# HBridge_Design.net
KiCad netlist of a schematic drawn in Altium Designer
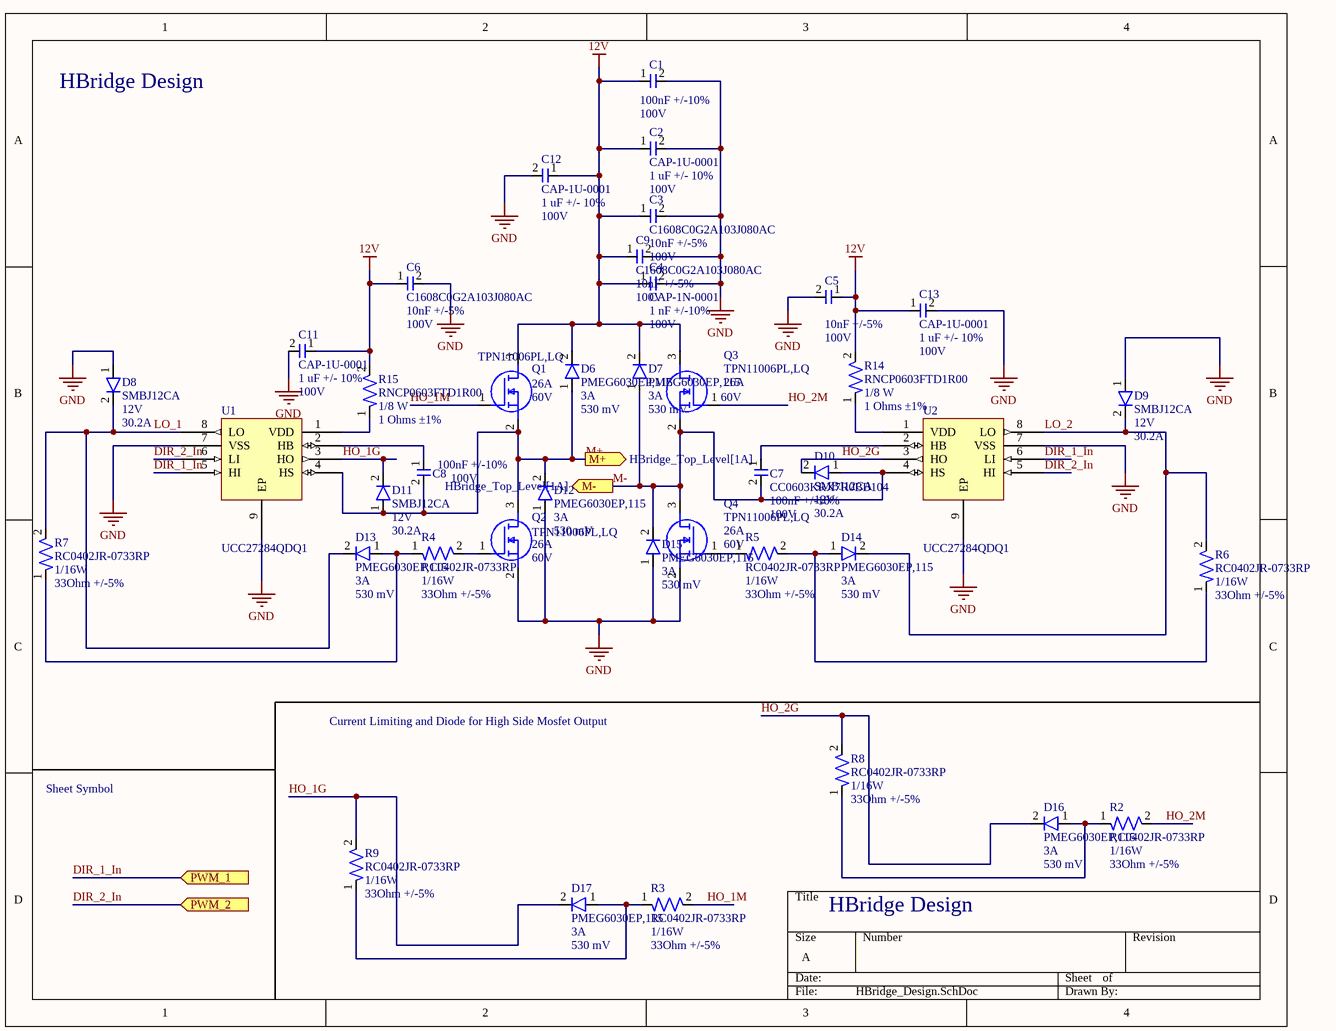
[diagram p0: HBridge_Design.SchDoc]

(export (version "E")
  (design (tool "Eeschema 10.0.6"))
  (components
    (comp (ref "C1")
      (value "CC0603KRX7R0BB104")
      (footprint "CAP-0603")
      (description "CAP CER 0.1UF 100V X7R 0603")
      (fields
        (field (name "MANUFACTURER") "YAGEO")
        (field (name "CAPACITANCE") "100nF +/-10%")
        (field (name "VOLTAGE RATING") "100V")
      )
      (libsource (lib "MasterLib") (part "CAP-100N-0001"))
    )
    (comp (ref "C2")
      (value "CAP-1U-0001")
      (footprint "CAP-1206 - duplicate")
      (description "1 µF ±10% 100V Ceramic Capacitor X7R 1206 (3216 Metric)")
      (fields (field (name "CAPACITANCE") "1 uF +/- 10%") (field (name "VOLTAGE") "100V"))
      (libsource (lib "MasterLib") (part "CAP-1U-0001"))
    )
    (comp (ref "C3")
      (value "C1608C0G2A103J080AC")
      (footprint "CAP-0603")
      (description "CAP CER 10000PF 100V C0G 0603")
      (fields
        (field (name "MANUFACTURER") "TDK Corporation")
        (field (name "CAPACITANCE") "10nF +/-5%")
        (field (name "VOLTAGE RATING") "100V")
      )
      (libsource (lib "MasterLib") (part "CAP-10N-0002"))
    )
    (comp (ref "C4")
      (value "CAP-1N-0001")
      (footprint "CAP-0603")
      (description "1000 pF ±10% 100V Ceramic Capacitor X7R 0603 (1608 Metric)")
      (fields (field (name "CAPACITANCE") "1 nF +/-10%") (field (name "VOLTAGE") "100V"))
      (libsource (lib "MasterLib") (part "CAP-1N-0001"))
    )
    (comp (ref "C5")
      (value "C1608C0G2A103J080AC")
      (footprint "CAP-0603")
      (description "CAP CER 10000PF 100V C0G 0603")
      (fields
        (field (name "MANUFACTURER") "TDK Corporation")
        (field (name "CAPACITANCE") "10nF +/-5%")
        (field (name "VOLTAGE RATING") "100V")
      )
      (libsource (lib "MasterLib") (part "CAP-10N-0002"))
    )
    (comp (ref "C6")
      (value "C1608C0G2A103J080AC")
      (footprint "CAP-0603")
      (description "CAP CER 10000PF 100V C0G 0603")
      (fields
        (field (name "MANUFACTURER") "TDK Corporation")
        (field (name "CAPACITANCE") "10nF +/-5%")
        (field (name "VOLTAGE RATING") "100V")
      )
      (libsource (lib "MasterLib") (part "CAP-10N-0002"))
    )
    (comp (ref "C7")
      (value "CC0603KRX7R0BB104")
      (footprint "CAP-0603")
      (description "CAP CER 0.1UF 100V X7R 0603")
      (fields
        (field (name "MANUFACTURER") "YAGEO")
        (field (name "CAPACITANCE") "100nF +/-10%")
        (field (name "VOLTAGE RATING") "100V")
      )
      (libsource (lib "MasterLib") (part "CAP-100N-0001"))
    )
    (comp (ref "C8")
      (value "CC0603KRX7R0BB104")
      (footprint "CAP-0603")
      (description "CAP CER 0.1UF 100V X7R 0603")
      (fields
        (field (name "MANUFACTURER") "YAGEO")
        (field (name "CAPACITANCE") "100nF +/-10%")
        (field (name "VOLTAGE RATING") "100V")
      )
      (libsource (lib "MasterLib") (part "CAP-100N-0001"))
    )
    (comp (ref "C9")
      (value "C1608C0G2A103J080AC")
      (footprint "CAP-0603")
      (description "CAP CER 10000PF 100V C0G 0603")
      (fields
        (field (name "MANUFACTURER") "TDK Corporation")
        (field (name "CAPACITANCE") "10nF +/-5%")
        (field (name "VOLTAGE RATING") "100V")
      )
      (libsource (lib "MasterLib") (part "CAP-10N-0002"))
    )
    (comp (ref "C11")
      (value "CAP-1U-0001")
      (footprint "CAP-1206 - duplicate")
      (description "1 µF ±10% 100V Ceramic Capacitor X7R 1206 (3216 Metric)")
      (fields (field (name "CAPACITANCE") "1 uF +/- 10%") (field (name "VOLTAGE") "100V"))
      (libsource (lib "MasterLib") (part "CAP-1U-0001"))
    )
    (comp (ref "C12")
      (value "CAP-1U-0001")
      (footprint "CAP-1206 - duplicate")
      (description "1 µF ±10% 100V Ceramic Capacitor X7R 1206 (3216 Metric)")
      (fields (field (name "CAPACITANCE") "1 uF +/- 10%") (field (name "VOLTAGE") "100V"))
      (libsource (lib "MasterLib") (part "CAP-1U-0001"))
    )
    (comp (ref "C13")
      (value "CAP-1U-0001")
      (footprint "CAP-1206 - duplicate")
      (description "1 µF ±10% 100V Ceramic Capacitor X7R 1206 (3216 Metric)")
      (fields (field (name "CAPACITANCE") "1 uF +/- 10%") (field (name "VOLTAGE") "100V"))
      (libsource (lib "MasterLib") (part "CAP-1U-0001"))
    )
    (comp (ref "D6")
      (value "PMEG6030EP,115")
      (footprint "DIO-SOD128")
      (description "Diode Schottky 60 V 3A Surface Mount SOD-128/CFP5")
      (fields
        (field (name "MANUFACTURER") "Nexperia USA Inc.")
        (field (name "CURRENT RATING") "3A")
        (field (name "VF (VOLTAGE FORWARD)") "530 mV")
      )
      (libsource (lib "MasterLib") (part "DIO-0.53V-0001"))
    )
    (comp (ref "D7")
      (value "PMEG6030EP,115")
      (footprint "DIO-SOD128")
      (description "Diode Schottky 60 V 3A Surface Mount SOD-128/CFP5")
      (fields
        (field (name "MANUFACTURER") "Nexperia USA Inc.")
        (field (name "CURRENT RATING") "3A")
        (field (name "VF (VOLTAGE FORWARD)") "530 mV")
      )
      (libsource (lib "MasterLib") (part "DIO-0.53V-0001"))
    )
    (comp (ref "D8")
      (value "SMBJ12CA")
      (footprint "DO-214AA (SMBJ)")
      (description "19.9V Clamp 30.2A Ipp Tvs Diode Surface Mount DO-214AA (SMBJ)")
      (fields
        (field (name "MANUFACTURER") "Littlefuse Inc.")
        (field (name "STANDOFF VOLTAGE") "12V")
        (field (name "CURRENT RATING") "30.2A")
      )
      (libsource (lib "MasterLib") (part "DIO-19.9V-0001"))
    )
    (comp (ref "D9")
      (value "SMBJ12CA")
      (footprint "DO-214AA (SMBJ)")
      (description "19.9V Clamp 30.2A Ipp Tvs Diode Surface Mount DO-214AA (SMBJ)")
      (fields
        (field (name "MANUFACTURER") "Littlefuse Inc.")
        (field (name "STANDOFF VOLTAGE") "12V")
        (field (name "CURRENT RATING") "30.2A")
      )
      (libsource (lib "MasterLib") (part "DIO-19.9V-0001"))
    )
    (comp (ref "D10")
      (value "SMBJ12CA")
      (footprint "DO-214AA (SMBJ)")
      (description "19.9V Clamp 30.2A Ipp Tvs Diode Surface Mount DO-214AA (SMBJ)")
      (fields
        (field (name "MANUFACTURER") "Littlefuse Inc.")
        (field (name "STANDOFF VOLTAGE") "12V")
        (field (name "CURRENT RATING") "30.2A")
      )
      (libsource (lib "MasterLib") (part "DIO-19.9V-0001"))
    )
    (comp (ref "D11")
      (value "SMBJ12CA")
      (footprint "DO-214AA (SMBJ)")
      (description "19.9V Clamp 30.2A Ipp Tvs Diode Surface Mount DO-214AA (SMBJ)")
      (fields
        (field (name "MANUFACTURER") "Littlefuse Inc.")
        (field (name "STANDOFF VOLTAGE") "12V")
        (field (name "CURRENT RATING") "30.2A")
      )
      (libsource (lib "MasterLib") (part "DIO-19.9V-0001"))
    )
    (comp (ref "D12")
      (value "PMEG6030EP,115")
      (footprint "DIO-SOD128")
      (description "Diode Schottky 60 V 3A Surface Mount SOD-128/CFP5")
      (fields
        (field (name "MANUFACTURER") "Nexperia USA Inc.")
        (field (name "CURRENT RATING") "3A")
        (field (name "VF (VOLTAGE FORWARD)") "530 mV")
      )
      (libsource (lib "MasterLib") (part "DIO-0.53V-0001"))
    )
    (comp (ref "D13")
      (value "PMEG6030EP,115")
      (footprint "DIO-SOD128")
      (description "Diode Schottky 60 V 3A Surface Mount SOD-128/CFP5")
      (fields
        (field (name "MANUFACTURER") "Nexperia USA Inc.")
        (field (name "CURRENT RATING") "3A")
        (field (name "VF (VOLTAGE FORWARD)") "530 mV")
      )
      (libsource (lib "MasterLib") (part "DIO-0.53V-0001"))
    )
    (comp (ref "D14")
      (value "PMEG6030EP,115")
      (footprint "DIO-SOD128")
      (description "Diode Schottky 60 V 3A Surface Mount SOD-128/CFP5")
      (fields
        (field (name "MANUFACTURER") "Nexperia USA Inc.")
        (field (name "CURRENT RATING") "3A")
        (field (name "VF (VOLTAGE FORWARD)") "530 mV")
      )
      (libsource (lib "MasterLib") (part "DIO-0.53V-0001"))
    )
    (comp (ref "D15")
      (value "PMEG6030EP,115")
      (footprint "DIO-SOD128")
      (description "Diode Schottky 60 V 3A Surface Mount SOD-128/CFP5")
      (fields
        (field (name "MANUFACTURER") "Nexperia USA Inc.")
        (field (name "CURRENT RATING") "3A")
        (field (name "VF (VOLTAGE FORWARD)") "530 mV")
      )
      (libsource (lib "MasterLib") (part "DIO-0.53V-0001"))
    )
    (comp (ref "D16")
      (value "PMEG6030EP,115")
      (footprint "DIO-SOD128")
      (description "Diode Schottky 60 V 3A Surface Mount SOD-128/CFP5")
      (fields
        (field (name "MANUFACTURER") "Nexperia USA Inc.")
        (field (name "CURRENT RATING") "3A")
        (field (name "VF (VOLTAGE FORWARD)") "530 mV")
      )
      (libsource (lib "MasterLib") (part "DIO-0.53V-0001"))
    )
    (comp (ref "D17")
      (value "PMEG6030EP,115")
      (footprint "DIO-SOD128")
      (description "Diode Schottky 60 V 3A Surface Mount SOD-128/CFP5")
      (fields
        (field (name "MANUFACTURER") "Nexperia USA Inc.")
        (field (name "CURRENT RATING") "3A")
        (field (name "VF (VOLTAGE FORWARD)") "530 mV")
      )
      (libsource (lib "MasterLib") (part "DIO-0.53V-0001"))
    )
    (comp (ref "Q1")
      (value "TPN11006PL,LQ")
      (footprint "NMOS-8TSON")
      (description "MOSFET N-CH 60V 200MA SOT23")
      (fields
        (field (name "MANUFACTURER") "Toshiba")
        (field (name "ID-CONTINUOUS") "26A")
        (field (name "VDS-MAX") "60V")
      )
      (libsource (lib "MasterLib") (part "NMOS-26A-0001"))
    )
    (comp (ref "Q2")
      (value "TPN11006PL,LQ")
      (footprint "NMOS-8TSON")
      (description "MOSFET N-CH 60V 200MA SOT23")
      (fields
        (field (name "MANUFACTURER") "Toshiba")
        (field (name "ID-CONTINUOUS") "26A")
        (field (name "VDS-MAX") "60V")
      )
      (libsource (lib "MasterLib") (part "NMOS-26A-0001"))
    )
    (comp (ref "Q3")
      (value "TPN11006PL,LQ")
      (footprint "NMOS-8TSON")
      (description "MOSFET N-CH 60V 200MA SOT23")
      (fields
        (field (name "MANUFACTURER") "Toshiba")
        (field (name "ID-CONTINUOUS") "26A")
        (field (name "VDS-MAX") "60V")
      )
      (libsource (lib "MasterLib") (part "NMOS-26A-0001"))
    )
    (comp (ref "Q4")
      (value "TPN11006PL,LQ")
      (footprint "NMOS-8TSON")
      (description "MOSFET N-CH 60V 200MA SOT23")
      (fields
        (field (name "MANUFACTURER") "Toshiba")
        (field (name "ID-CONTINUOUS") "26A")
        (field (name "VDS-MAX") "60V")
      )
      (libsource (lib "MasterLib") (part "NMOS-26A-0001"))
    )
    (comp (ref "R2")
      (value "RC0402JR-0733RP")
      (footprint "RES-0402")
      (description "RES SMD 33 OHM 5% 1/16W 0402")
      (fields
        (field (name "MANUFACTURER") "YAGEO")
        (field (name "POWER RATING") "1/16W")
        (field (name "RESISTANCE") "33Ohm +/-5%")
      )
      (libsource (lib "MasterLib") (part "RES-33-0001"))
    )
    (comp (ref "R3")
      (value "RC0402JR-0733RP")
      (footprint "RES-0402")
      (description "RES SMD 33 OHM 5% 1/16W 0402")
      (fields
        (field (name "MANUFACTURER") "YAGEO")
        (field (name "POWER RATING") "1/16W")
        (field (name "RESISTANCE") "33Ohm +/-5%")
      )
      (libsource (lib "MasterLib") (part "RES-33-0001"))
    )
    (comp (ref "R4")
      (value "RC0402JR-0733RP")
      (footprint "RES-0402")
      (description "RES SMD 33 OHM 5% 1/16W 0402")
      (fields
        (field (name "MANUFACTURER") "YAGEO")
        (field (name "POWER RATING") "1/16W")
        (field (name "RESISTANCE") "33Ohm +/-5%")
      )
      (libsource (lib "MasterLib") (part "RES-33-0001"))
    )
    (comp (ref "R5")
      (value "RC0402JR-0733RP")
      (footprint "RES-0402")
      (description "RES SMD 33 OHM 5% 1/16W 0402")
      (fields
        (field (name "MANUFACTURER") "YAGEO")
        (field (name "POWER RATING") "1/16W")
        (field (name "RESISTANCE") "33Ohm +/-5%")
      )
      (libsource (lib "MasterLib") (part "RES-33-0001"))
    )
    (comp (ref "R6")
      (value "RC0402JR-0733RP")
      (footprint "RES-0402")
      (description "RES SMD 33 OHM 5% 1/16W 0402")
      (fields
        (field (name "MANUFACTURER") "YAGEO")
        (field (name "POWER RATING") "1/16W")
        (field (name "RESISTANCE") "33Ohm +/-5%")
      )
      (libsource (lib "MasterLib") (part "RES-33-0001"))
    )
    (comp (ref "R7")
      (value "RC0402JR-0733RP")
      (footprint "RES-0402")
      (description "RES SMD 33 OHM 5% 1/16W 0402")
      (fields
        (field (name "MANUFACTURER") "YAGEO")
        (field (name "POWER RATING") "1/16W")
        (field (name "RESISTANCE") "33Ohm +/-5%")
      )
      (libsource (lib "MasterLib") (part "RES-33-0001"))
    )
    (comp (ref "R8")
      (value "RC0402JR-0733RP")
      (footprint "RES-0402")
      (description "RES SMD 33 OHM 5% 1/16W 0402")
      (fields
        (field (name "MANUFACTURER") "YAGEO")
        (field (name "POWER RATING") "1/16W")
        (field (name "RESISTANCE") "33Ohm +/-5%")
      )
      (libsource (lib "MasterLib") (part "RES-33-0001"))
    )
    (comp (ref "R9")
      (value "RC0402JR-0733RP")
      (footprint "RES-0402")
      (description "RES SMD 33 OHM 5% 1/16W 0402")
      (fields
        (field (name "MANUFACTURER") "YAGEO")
        (field (name "POWER RATING") "1/16W")
        (field (name "RESISTANCE") "33Ohm +/-5%")
      )
      (libsource (lib "MasterLib") (part "RES-33-0001"))
    )
    (comp (ref "R14")
      (value "RNCP0603FTD1R00")
      (footprint "RES-0603")
      (description "1 Ohms ±1% 0.125W, 1/8W Chip Resistor 0603 (1608 Metric) Anti-Sulfur Thin Film")
      (fields (field (name "POWER") "1/8 W") (field (name "RESISTANCE") "1 Ohms ±1%"))
      (libsource (lib "MasterLib") (part "RES-1-0001"))
    )
    (comp (ref "R15")
      (value "RNCP0603FTD1R00")
      (footprint "RES-0603")
      (description "1 Ohms ±1% 0.125W, 1/8W Chip Resistor 0603 (1608 Metric) Anti-Sulfur Thin Film")
      (fields (field (name "POWER") "1/8 W") (field (name "RESISTANCE") "1 Ohms ±1%"))
      (libsource (lib "MasterLib") (part "RES-1-0001"))
    )
    (comp (ref "U1")
      (value "UCC27284QDQ1")
      (footprint "IC-BUCK-8SOIC")
      (fields (field (name "MANUFACTURER") "Texas Instruments"))
      (libsource (lib "") (part "IC-GDRV-0001_1"))
    )
    (comp (ref "U2")
      (value "UCC27284QDQ1")
      (footprint "IC-BUCK-8SOIC")
      (fields (field (name "MANUFACTURER") "Texas Instruments"))
      (libsource (lib "MasterLib") (part "IC-GDRV-0001"))
    )
  )
  (nets
    (net (code "1") (name "/DIR_1_In") (class "Default")
      (node (ref "U1") (pin "5") (pinfunction "HI_5") (pintype "input"))
      (node (ref "U2") (pin "6") (pinfunction "LI_6") (pintype "input"))
    )
    (net (code "2") (name "/DIR_2_In") (class "Default")
      (node (ref "U1") (pin "6") (pinfunction "LI_6") (pintype "input"))
      (node (ref "U2") (pin "5") (pinfunction "HI_5") (pintype "input"))
    )
    (net (code "3") (name "/HO_1G") (class "Default")
      (node (ref "D11") (pin "2") (pintype "passive"))
      (node (ref "D17") (pin "2") (pintype "passive"))
      (node (ref "R9") (pin "2") (pinfunction "2_2") (pintype "passive"))
      (node (ref "U1") (pin "3") (pinfunction "HO_3") (pintype "output"))
    )
    (net (code "4") (name "/HO_1M") (class "Default")
      (node (ref "Q1") (pin "1") (pinfunction "G_1") (pintype "passive"))
      (node (ref "R3") (pin "2") (pinfunction "2_2") (pintype "passive"))
    )
    (net (code "5") (name "/HO_2G") (class "Default")
      (node (ref "D10") (pin "2") (pintype "passive"))
      (node (ref "D16") (pin "2") (pintype "passive"))
      (node (ref "R8") (pin "2") (pinfunction "2_2") (pintype "passive"))
      (node (ref "U2") (pin "3") (pinfunction "HO_3") (pintype "output"))
    )
    (net (code "6") (name "/HO_2M") (class "Default")
      (node (ref "Q3") (pin "1") (pinfunction "G_1") (pintype "passive"))
      (node (ref "R2") (pin "2") (pinfunction "2_2") (pintype "passive"))
    )
    (net (code "7") (name "/LO_1") (class "Default")
      (node (ref "D13") (pin "2") (pintype "passive"))
      (node (ref "D8") (pin "2") (pintype "passive"))
      (node (ref "R7") (pin "2") (pinfunction "2_2") (pintype "passive"))
      (node (ref "U1") (pin "8") (pinfunction "LO_8") (pintype "output"))
    )
    (net (code "8") (name "/LO_2") (class "Default")
      (node (ref "D14") (pin "2") (pintype "passive"))
      (node (ref "D9") (pin "2") (pintype "passive"))
      (node (ref "R6") (pin "2") (pinfunction "2_2") (pintype "passive"))
      (node (ref "U2") (pin "8") (pinfunction "LO_8") (pintype "output"))
    )
    (net (code "9") (name "/M+") (class "Default")
      (node (ref "C8") (pin "2") (pinfunction "2_2") (pintype "passive"))
      (node (ref "D11") (pin "1") (pintype "passive"))
      (node (ref "D12") (pin "2") (pintype "passive"))
      (node (ref "D6") (pin "1") (pintype "passive"))
      (node (ref "Q1") (pin "2") (pinfunction "S_2") (pintype "passive"))
      (node (ref "Q2") (pin "3") (pinfunction "D_3") (pintype "passive"))
      (node (ref "U1") (pin "4") (pinfunction "HS_4") (pintype "bidirectional"))
    )
    (net (code "10") (name "/M-") (class "Default")
      (node (ref "C7") (pin "2") (pinfunction "2_2") (pintype "passive"))
      (node (ref "D10") (pin "1") (pintype "passive"))
      (node (ref "D15") (pin "2") (pintype "passive"))
      (node (ref "D7") (pin "1") (pintype "passive"))
      (node (ref "Q3") (pin "2") (pinfunction "S_2") (pintype "passive"))
      (node (ref "Q4") (pin "3") (pinfunction "D_3") (pintype "passive"))
      (node (ref "U2") (pin "4") (pinfunction "HS_4") (pintype "bidirectional"))
    )
    (net (code "11") (name "12V") (class "Default")
      (node (ref "C1") (pin "1") (pinfunction "1_1") (pintype "passive"))
      (node (ref "C11") (pin "1") (pinfunction "1_1") (pintype "passive"))
      (node (ref "C12") (pin "1") (pinfunction "1_1") (pintype "passive"))
      (node (ref "C13") (pin "1") (pinfunction "1_1") (pintype "passive"))
      (node (ref "C2") (pin "1") (pinfunction "1_1") (pintype "passive"))
      (node (ref "C3") (pin "1") (pinfunction "1_1") (pintype "passive"))
      (node (ref "C4") (pin "1") (pinfunction "1_1") (pintype "passive"))
      (node (ref "C5") (pin "1") (pinfunction "1_1") (pintype "passive"))
      (node (ref "C6") (pin "1") (pinfunction "1_1") (pintype "passive"))
      (node (ref "C9") (pin "1") (pinfunction "1_1") (pintype "passive"))
      (node (ref "D6") (pin "2") (pintype "passive"))
      (node (ref "D7") (pin "2") (pintype "passive"))
      (node (ref "Q1") (pin "3") (pinfunction "D_3") (pintype "passive"))
      (node (ref "Q3") (pin "3") (pinfunction "D_3") (pintype "passive"))
      (node (ref "R14") (pin "2") (pinfunction "2_2") (pintype "passive"))
      (node (ref "R15") (pin "2") (pinfunction "2_2") (pintype "passive"))
    )
    (net (code "12") (name "GND") (class "Default")
      (node (ref "C1") (pin "2") (pinfunction "2_2") (pintype "passive"))
      (node (ref "C11") (pin "2") (pinfunction "2_2") (pintype "passive"))
      (node (ref "C12") (pin "2") (pinfunction "2_2") (pintype "passive"))
      (node (ref "C13") (pin "2") (pinfunction "2_2") (pintype "passive"))
      (node (ref "C2") (pin "2") (pinfunction "2_2") (pintype "passive"))
      (node (ref "C3") (pin "2") (pinfunction "2_2") (pintype "passive"))
      (node (ref "C4") (pin "2") (pinfunction "2_2") (pintype "passive"))
      (node (ref "C5") (pin "2") (pinfunction "2_2") (pintype "passive"))
      (node (ref "C6") (pin "2") (pinfunction "2_2") (pintype "passive"))
      (node (ref "C9") (pin "2") (pinfunction "2_2") (pintype "passive"))
      (node (ref "D12") (pin "1") (pintype "passive"))
      (node (ref "D15") (pin "1") (pintype "passive"))
      (node (ref "D8") (pin "1") (pintype "passive"))
      (node (ref "D9") (pin "1") (pintype "passive"))
      (node (ref "Q2") (pin "2") (pinfunction "S_2") (pintype "passive"))
      (node (ref "Q4") (pin "2") (pinfunction "S_2") (pintype "passive"))
      (node (ref "U1") (pin "7") (pinfunction "VSS_7") (pintype "power_in"))
      (node (ref "U1") (pin "9") (pinfunction "EP_9") (pintype "power_in"))
      (node (ref "U2") (pin "7") (pinfunction "VSS_7") (pintype "power_in"))
      (node (ref "U2") (pin "9") (pinfunction "EP_9") (pintype "power_in"))
    )
    (net (code "13") (name "Net-(D13-Pad1)") (class "Default")
      (node (ref "D13") (pin "1") (pintype "passive"))
      (node (ref "R4") (pin "1") (pinfunction "1_1") (pintype "passive"))
      (node (ref "R7") (pin "1") (pinfunction "1_1") (pintype "passive"))
    )
    (net (code "14") (name "Net-(D14-Pad1)") (class "Default")
      (node (ref "D14") (pin "1") (pintype "passive"))
      (node (ref "R5") (pin "2") (pinfunction "2_2") (pintype "passive"))
      (node (ref "R6") (pin "1") (pinfunction "1_1") (pintype "passive"))
    )
    (net (code "15") (name "Net-(D16-Pad1)") (class "Default")
      (node (ref "D16") (pin "1") (pintype "passive"))
      (node (ref "R2") (pin "1") (pinfunction "1_1") (pintype "passive"))
      (node (ref "R8") (pin "1") (pinfunction "1_1") (pintype "passive"))
    )
    (net (code "16") (name "Net-(D17-Pad1)") (class "Default")
      (node (ref "D17") (pin "1") (pintype "passive"))
      (node (ref "R3") (pin "1") (pinfunction "1_1") (pintype "passive"))
      (node (ref "R9") (pin "1") (pinfunction "1_1") (pintype "passive"))
    )
    (net (code "17") (name "Net-(Q2-G)") (class "Default")
      (node (ref "Q2") (pin "1") (pinfunction "G_1") (pintype "passive"))
      (node (ref "R4") (pin "2") (pinfunction "2_2") (pintype "passive"))
    )
    (net (code "18") (name "Net-(Q4-G)") (class "Default")
      (node (ref "Q4") (pin "1") (pinfunction "G_1") (pintype "passive"))
      (node (ref "R5") (pin "1") (pinfunction "1_1") (pintype "passive"))
    )
    (net (code "19") (name "Net-(U1-HB)") (class "Default")
      (node (ref "C8") (pin "1") (pinfunction "1_1") (pintype "passive"))
      (node (ref "U1") (pin "2") (pinfunction "HB_2") (pintype "bidirectional"))
    )
    (net (code "20") (name "Net-(U1-VDD)") (class "Default")
      (node (ref "R15") (pin "1") (pinfunction "1_1") (pintype "passive"))
      (node (ref "U1") (pin "1") (pinfunction "VDD_1") (pintype "power_in"))
    )
    (net (code "21") (name "Net-(U2-HB)") (class "Default")
      (node (ref "C7") (pin "1") (pinfunction "1_1") (pintype "passive"))
      (node (ref "U2") (pin "2") (pinfunction "HB_2") (pintype "bidirectional"))
    )
    (net (code "22") (name "Net-(U2-VDD)") (class "Default")
      (node (ref "R14") (pin "1") (pinfunction "1_1") (pintype "passive"))
      (node (ref "U2") (pin "1") (pinfunction "VDD_1") (pintype "power_in"))
    )
  )
)
